# pci.net
KiCad netlist of a schematic drawn in EAGLE
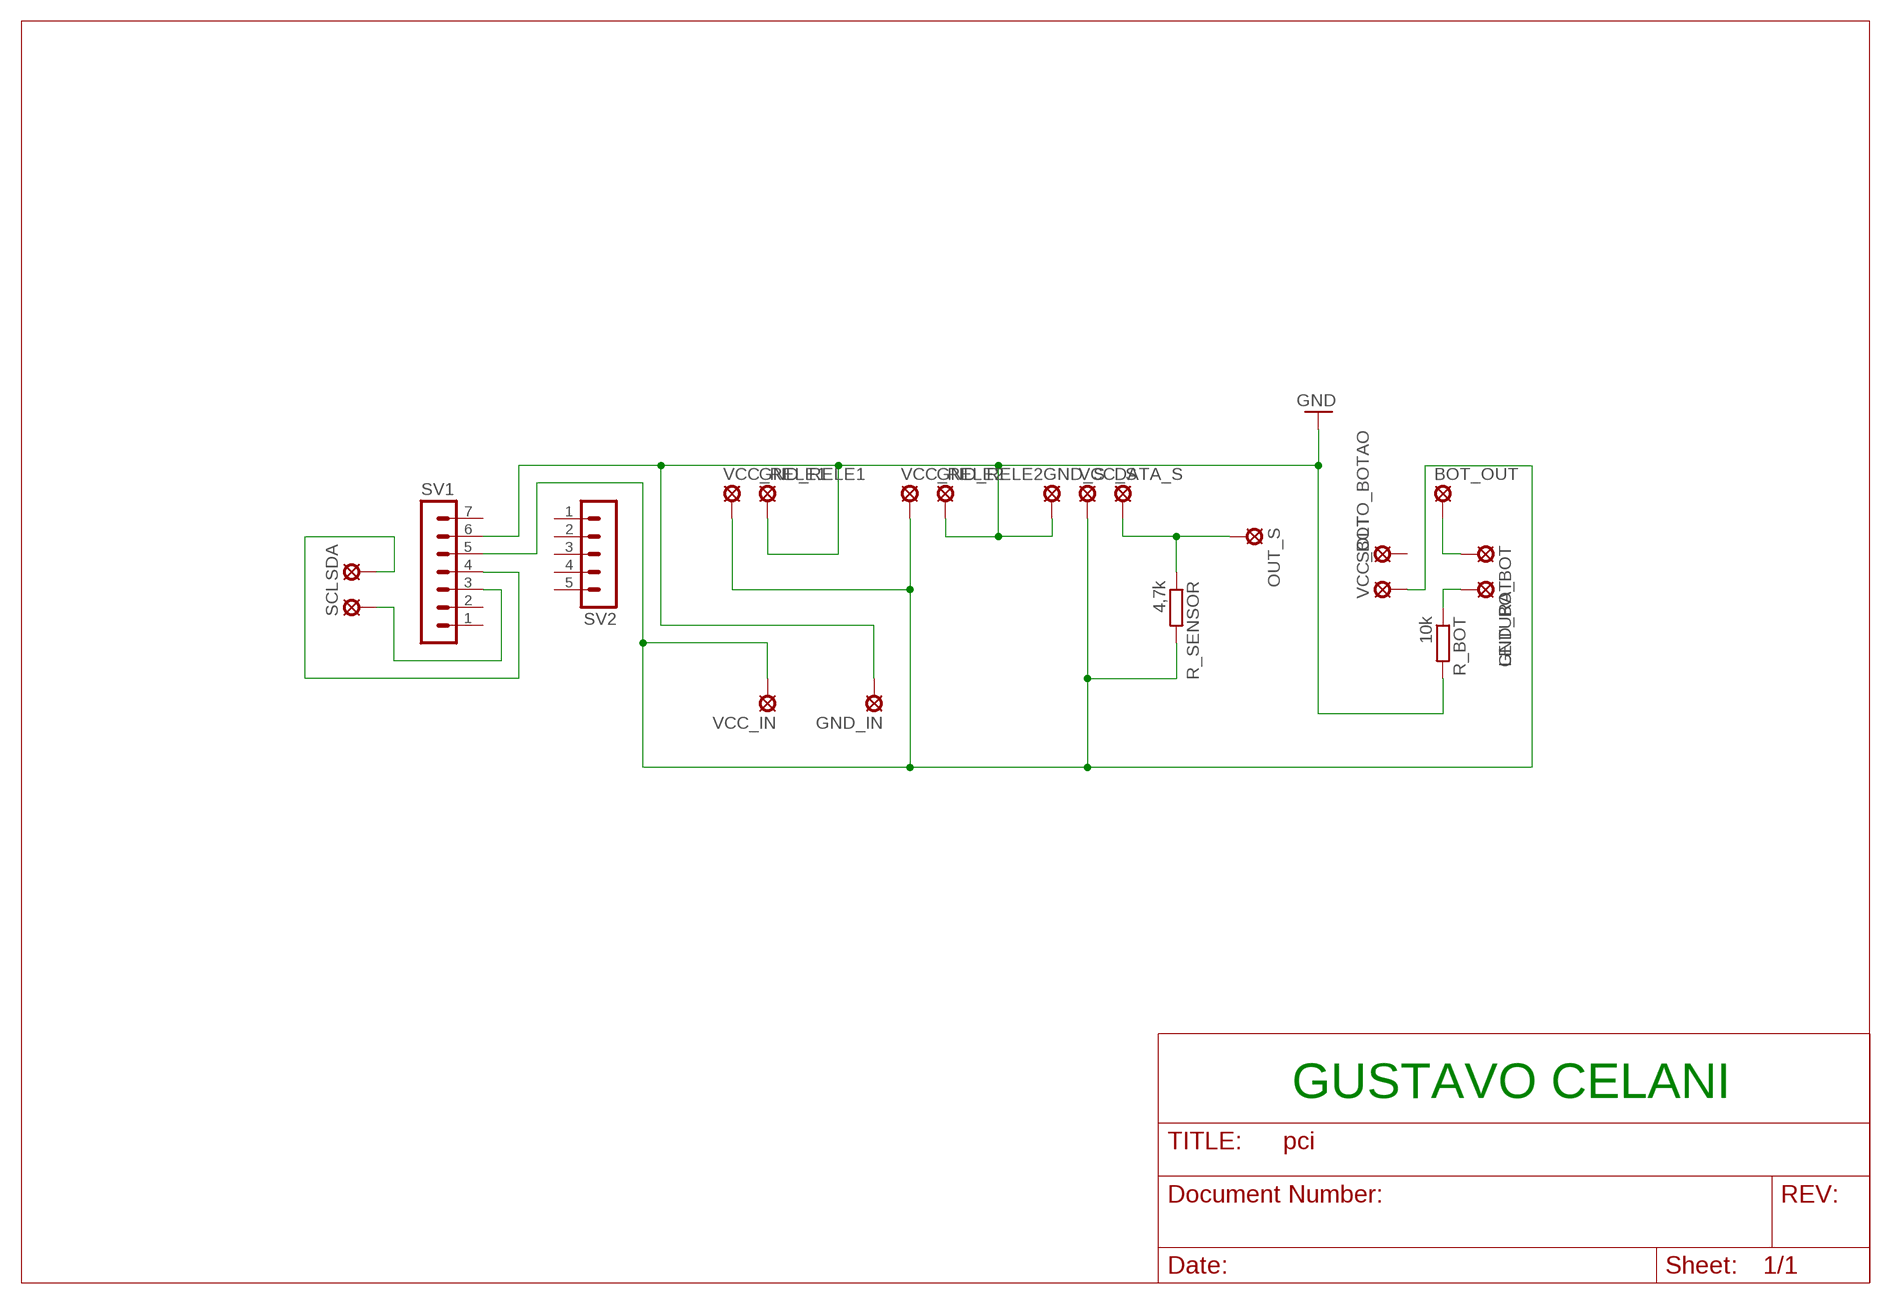
[diagram p0: schematic, sheet 1]

(export (version "E")
  (design (tool "Eeschema 10.0.6"))
  (components
    (comp (ref "BOT_OUT")
      (value "SE11")
      (footprint "eagle-import:SE11")
      (libsource (lib "eagle-import") (part "SE11"))
    )
    (comp (ref "DATA_S")
      (value "SE11")
      (footprint "eagle-import:SE11")
      (libsource (lib "eagle-import") (part "SE11"))
    )
    (comp (ref "GND_BOT")
      (value "SE11")
      (footprint "eagle-import:SE11")
      (libsource (lib "eagle-import") (part "SE11"))
    )
    (comp (ref "GND_IN")
      (value "SE11")
      (footprint "eagle-import:SE11")
      (libsource (lib "eagle-import") (part "SE11"))
    )
    (comp (ref "GND_RELE1")
      (value "SE11")
      (footprint "eagle-import:SE11")
      (libsource (lib "eagle-import") (part "SE11"))
    )
    (comp (ref "GND_RELE2")
      (value "SE11")
      (footprint "eagle-import:SE11")
      (libsource (lib "eagle-import") (part "SE11"))
    )
    (comp (ref "GND_S")
      (value "SE11")
      (footprint "eagle-import:SE11")
      (libsource (lib "eagle-import") (part "SE11"))
    )
    (comp (ref "LEITURA_BOT")
      (value "SE11")
      (footprint "eagle-import:SE11")
      (libsource (lib "eagle-import") (part "SE11"))
    )
    (comp (ref "OUT_S")
      (value "SE11")
      (footprint "eagle-import:SE11")
      (libsource (lib "eagle-import") (part "SE11"))
    )
    (comp (ref "R_BOT")
      (value "10k")
      (footprint "eagle-import:0204_7")
      (libsource (lib "eagle-import") (part "R-EU_0204/7"))
    )
    (comp (ref "R_SENSOR")
      (value "4,7k")
      (footprint "eagle-import:0204_7")
      (libsource (lib "eagle-import") (part "R-EU_0204/7"))
    )
    (comp (ref "SCL")
      (value "SE11")
      (footprint "eagle-import:SE11")
      (libsource (lib "eagle-import") (part "SE11"))
    )
    (comp (ref "SDA")
      (value "SE11")
      (footprint "eagle-import:SE11")
      (libsource (lib "eagle-import") (part "SE11"))
    )
    (comp (ref "SOLTO_BOTAO")
      (value "SE11")
      (footprint "eagle-import:SE11")
      (libsource (lib "eagle-import") (part "SE11"))
    )
    (comp (ref "SV1")
      (value "MA07-1")
      (footprint "eagle-import:MA07-1")
      (libsource (lib "eagle-import") (part "MA07-1"))
    )
    (comp (ref "SV2")
      (value "MA05-1")
      (footprint "eagle-import:MA05-1")
      (libsource (lib "eagle-import") (part "MA05-1"))
    )
    (comp (ref "VCC_BOT")
      (value "SE11")
      (footprint "eagle-import:SE11")
      (libsource (lib "eagle-import") (part "SE11"))
    )
    (comp (ref "VCC_IN")
      (value "SE11")
      (footprint "eagle-import:SE11")
      (libsource (lib "eagle-import") (part "SE11"))
    )
    (comp (ref "VCC_RELE1")
      (value "SE11")
      (footprint "eagle-import:SE11")
      (libsource (lib "eagle-import") (part "SE11"))
    )
    (comp (ref "VCC_RELE2")
      (value "SE11")
      (footprint "eagle-import:SE11")
      (libsource (lib "eagle-import") (part "SE11"))
    )
    (comp (ref "VCC_S")
      (value "SE11")
      (footprint "eagle-import:SE11")
      (libsource (lib "eagle-import") (part "SE11"))
    )
  )
  (nets
    (net (code "1") (name "GND") (class "Default")
      (node (ref "GND_IN") (pin "MP") (pinfunction "MP_MP") (pintype "passive"))
      (node (ref "GND_RELE1") (pin "MP") (pinfunction "MP_MP") (pintype "passive"))
      (node (ref "GND_RELE2") (pin "MP") (pinfunction "MP_MP") (pintype "passive"))
      (node (ref "GND_S") (pin "MP") (pinfunction "MP_MP") (pintype "passive"))
      (node (ref "R_BOT") (pin "2") (pinfunction "2_2") (pintype "passive"))
      (node (ref "SV1") (pin "6") (pinfunction "6_6") (pintype "passive"))
    )
    (net (code "2") (name "Net-(BOT_OUT-PadMP)") (class "Default")
      (node (ref "BOT_OUT") (pin "MP") (pinfunction "MP_MP") (pintype "passive"))
      (node (ref "LEITURA_BOT") (pin "MP") (pinfunction "MP_MP") (pintype "passive"))
    )
    (net (code "3") (name "Net-(DATA_S-PadMP)") (class "Default")
      (node (ref "DATA_S") (pin "MP") (pinfunction "MP_MP") (pintype "passive"))
      (node (ref "OUT_S") (pin "MP") (pinfunction "MP_MP") (pintype "passive"))
      (node (ref "R_SENSOR") (pin "1") (pinfunction "1_1") (pintype "passive"))
    )
    (net (code "4") (name "Net-(GND_BOT-PadMP)") (class "Default")
      (node (ref "GND_BOT") (pin "MP") (pinfunction "MP_MP") (pintype "passive"))
      (node (ref "R_BOT") (pin "1") (pinfunction "1_1") (pintype "passive"))
    )
    (net (code "5") (name "Net-(R_SENSOR-Pad2)") (class "Default")
      (node (ref "R_SENSOR") (pin "2") (pinfunction "2_2") (pintype "passive"))
      (node (ref "SV1") (pin "5") (pinfunction "5_5") (pintype "passive"))
      (node (ref "VCC_BOT") (pin "MP") (pinfunction "MP_MP") (pintype "passive"))
      (node (ref "VCC_IN") (pin "MP") (pinfunction "MP_MP") (pintype "passive"))
      (node (ref "VCC_RELE1") (pin "MP") (pinfunction "MP_MP") (pintype "passive"))
      (node (ref "VCC_RELE2") (pin "MP") (pinfunction "MP_MP") (pintype "passive"))
      (node (ref "VCC_S") (pin "MP") (pinfunction "MP_MP") (pintype "passive"))
    )
    (net (code "6") (name "Net-(SCL-PadMP)") (class "Default")
      (node (ref "SCL") (pin "MP") (pinfunction "MP_MP") (pintype "passive"))
      (node (ref "SV1") (pin "3") (pinfunction "3_3") (pintype "passive"))
    )
    (net (code "7") (name "Net-(SDA-PadMP)") (class "Default")
      (node (ref "SDA") (pin "MP") (pinfunction "MP_MP") (pintype "passive"))
      (node (ref "SV1") (pin "4") (pinfunction "4_4") (pintype "passive"))
    )
    (net (code "8") (name "unconnected-(SOLTO_BOTAO-PadMP)") (class "Default")
      (node (ref "SOLTO_BOTAO") (pin "MP") (pinfunction "MP_MP") (pintype "passive"))
    )
    (net (code "9") (name "unconnected-(SV1-Pad1)") (class "Default")
      (node (ref "SV1") (pin "1") (pinfunction "1_1") (pintype "passive"))
    )
    (net (code "10") (name "unconnected-(SV1-Pad2)") (class "Default")
      (node (ref "SV1") (pin "2") (pinfunction "2_2") (pintype "passive"))
    )
    (net (code "11") (name "unconnected-(SV1-Pad7)") (class "Default")
      (node (ref "SV1") (pin "7") (pinfunction "7_7") (pintype "passive"))
    )
    (net (code "12") (name "unconnected-(SV2-Pad1)") (class "Default")
      (node (ref "SV2") (pin "1") (pinfunction "1_1") (pintype "passive"))
    )
    (net (code "13") (name "unconnected-(SV2-Pad2)") (class "Default")
      (node (ref "SV2") (pin "2") (pinfunction "2_2") (pintype "passive"))
    )
    (net (code "14") (name "unconnected-(SV2-Pad3)") (class "Default")
      (node (ref "SV2") (pin "3") (pinfunction "3_3") (pintype "passive"))
    )
    (net (code "15") (name "unconnected-(SV2-Pad4)") (class "Default")
      (node (ref "SV2") (pin "4") (pinfunction "4_4") (pintype "passive"))
    )
    (net (code "16") (name "unconnected-(SV2-Pad5)") (class "Default")
      (node (ref "SV2") (pin "5") (pinfunction "5_5") (pintype "passive"))
    )
  )
)
